# Other_funtions.net
KiCad netlist of a schematic drawn in Altium Designer
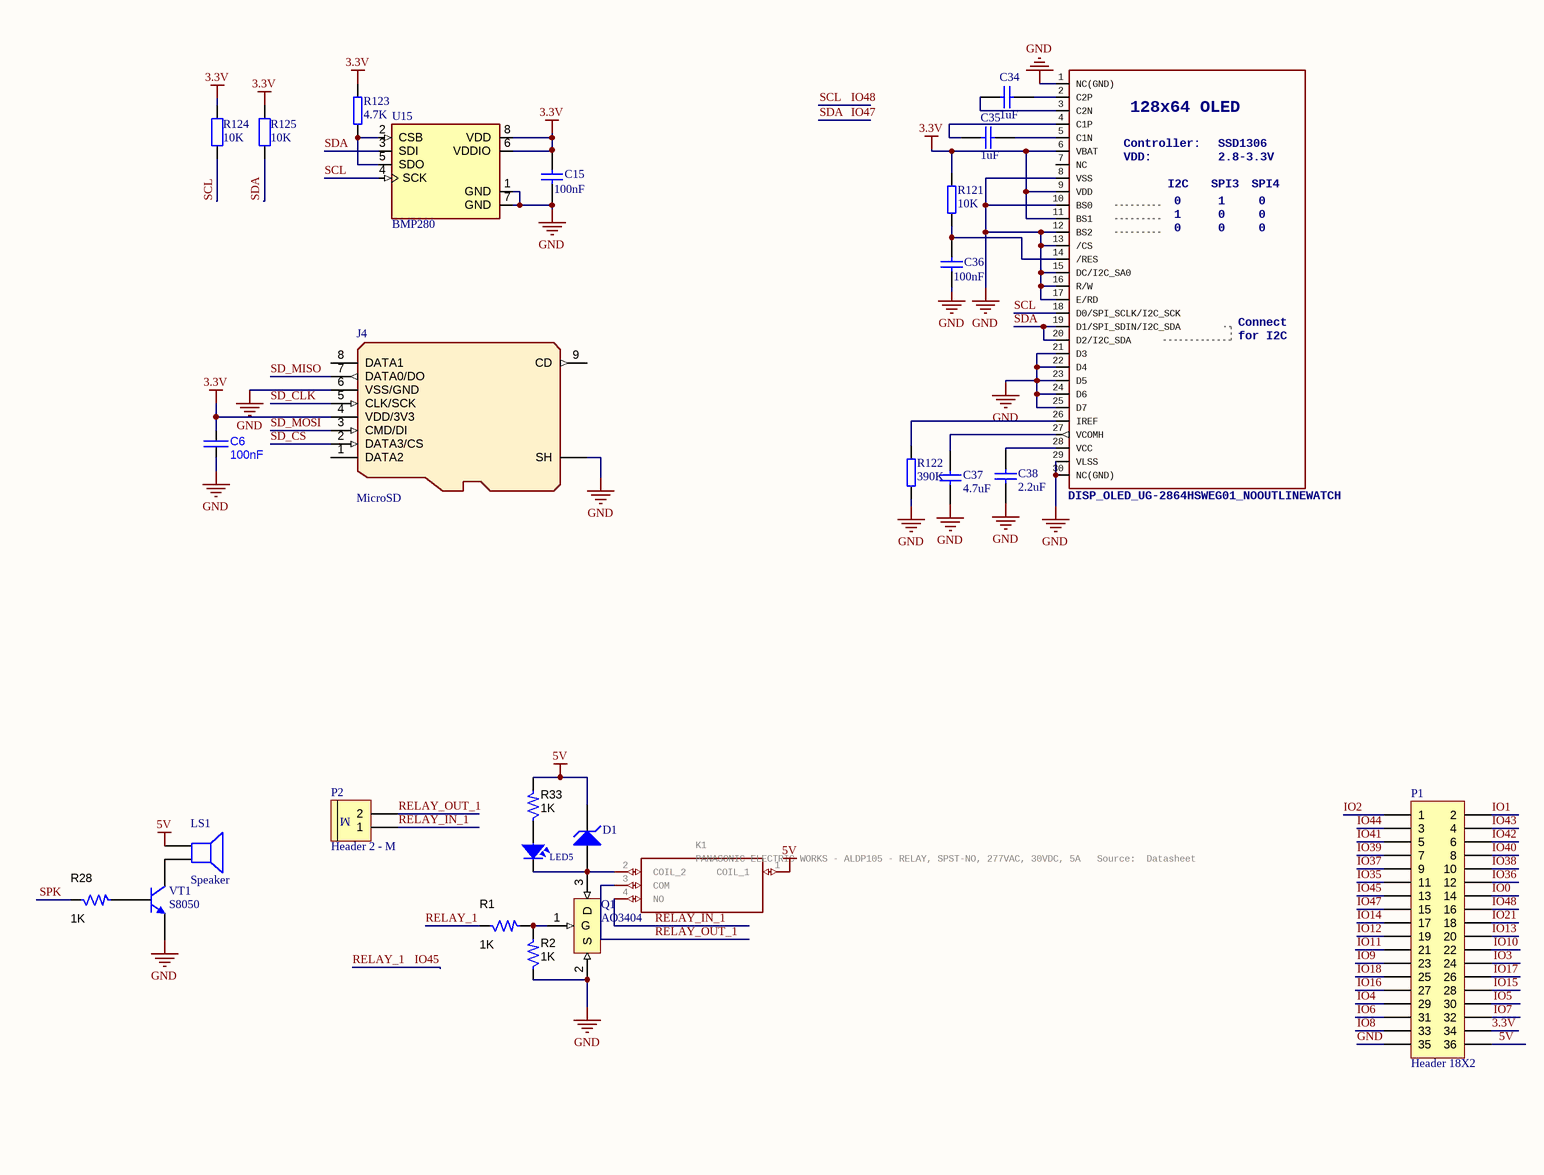
[diagram p0: Other_funtions.SchDoc, left]
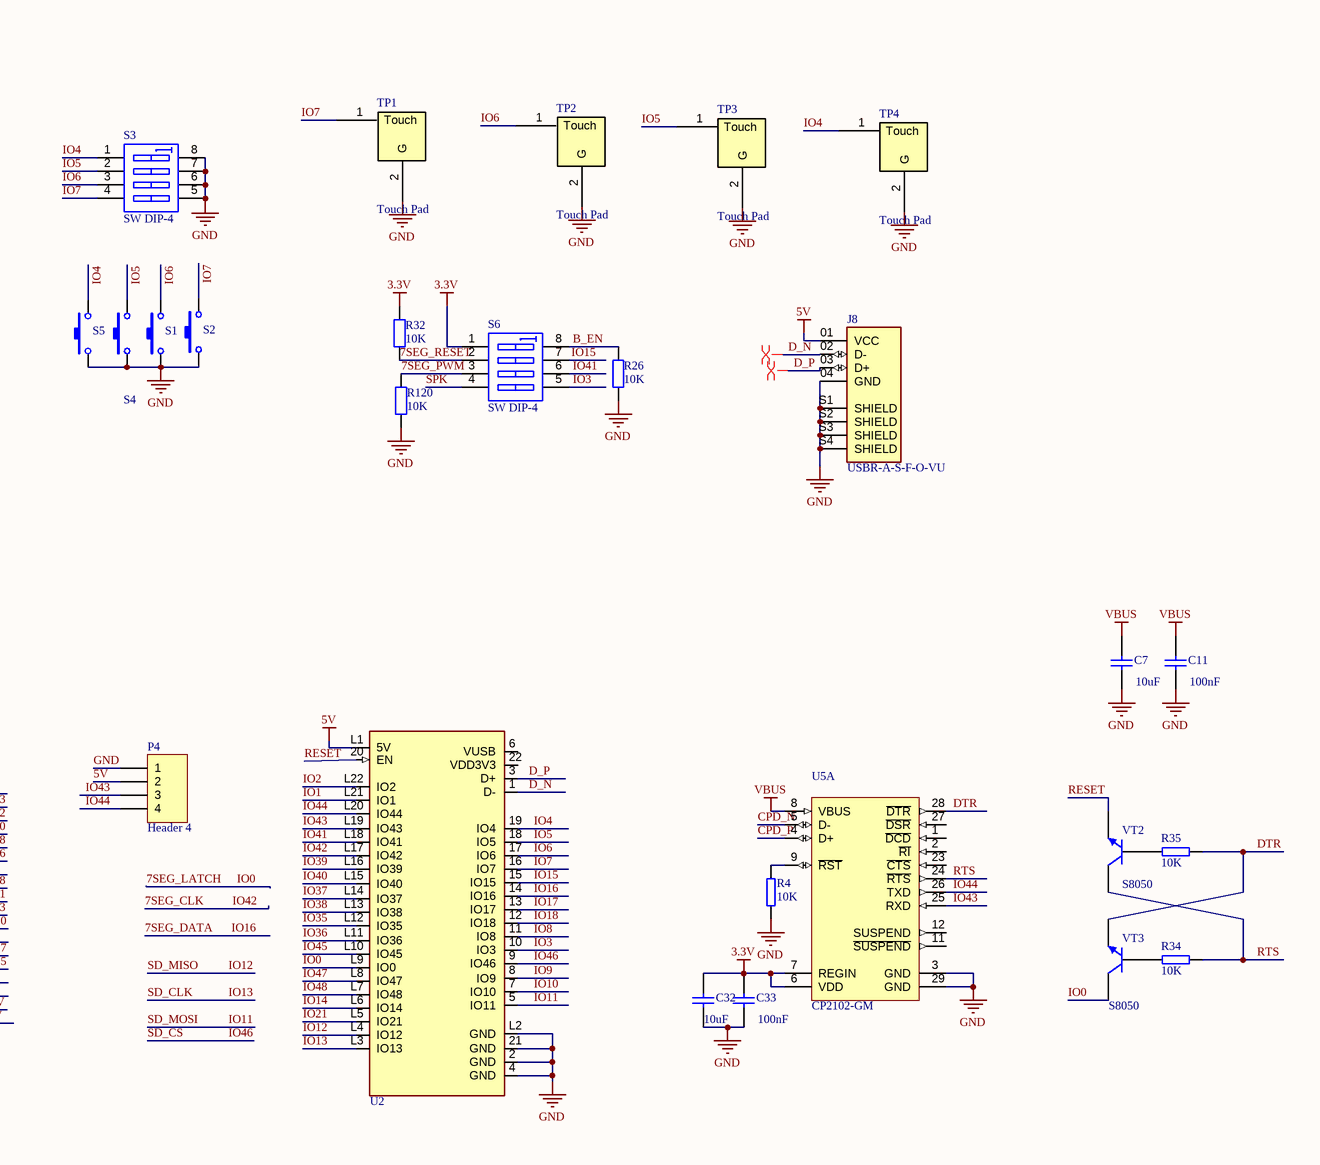
[diagram p1: Other_funtions.SchDoc, right]

(export (version "E")
  (design (tool "Eeschema 10.0.6"))
  (components
    (comp (ref "C6")
      (value "100nF")
      (footprint "CAPC2012X135N")
      (description "Capacitor SMD Cer 1.8nF 10% 50V X7R 0805")
      (fields (field (name "TOLERANCE") "±10%") (field (name "Comment") "approved sub OK"))
      (libsource (lib "WIle_dev_kit") (part "CAP C_0805"))
    )
    (comp (ref "C7")
      (value "10uF")
      (footprint "CAPC1608X90N")
      (description "CAP SM 0603 X5R 10uF 10%")
      (fields (field (name "TOLERANCE") "±10%") (field (name "Comment") "Cap Semi"))
      (libsource (lib "electronpowered") (part "CAP-SM-0603-X5R-10uF"))
    )
    (comp (ref "C11")
      (value "100nF")
      (footprint "CAPC1608X90N")
      (description "CAP SM 0603 X7R 100nF 10%")
      (fields (field (name "TOLERANCE") "±10%") (field (name "Comment") "Cap Semi"))
      (libsource (lib "electronpowered") (part "CAP-SM-0603-X7R-100nF"))
    )
    (comp (ref "C15")
      (value "100nF")
      (footprint "CAPC1608X90N")
      (description "CAP SM 0603 X7R 100nF 10%")
      (fields (field (name "TOLERANCE") "±10%") (field (name "Comment") "Cap Semi"))
      (libsource (lib "electronpowered") (part "CAP-SM-0603-X7R-100nF"))
    )
    (comp (ref "C32")
      (value "10uF")
      (footprint "CAPC1608X90N")
      (description "CAP SM 0603 X5R 10uF 10%")
      (fields (field (name "TOLERANCE") "±10%") (field (name "Comment") "Cap Semi"))
      (libsource (lib "electronpowered") (part "CAP-SM-0603-X5R-10uF"))
    )
    (comp (ref "C33")
      (value "100nF")
      (footprint "CAPC1608X90N")
      (description "CAP SM 0603 X7R 100nF 10%")
      (fields (field (name "TOLERANCE") "±10%") (field (name "Comment") "Cap Semi"))
      (libsource (lib "electronpowered") (part "CAP-SM-0603-X7R-100nF"))
    )
    (comp (ref "C34")
      (value "1uF")
      (footprint "CAPC1608X90N")
      (description "CAP SM 0603 X7R 100nF 10%")
      (fields (field (name "TOLERANCE") "±10%") (field (name "Comment") "Cap Semi"))
      (libsource (lib "electronpowered") (part "CAP-SM-0603-X7R-100nF"))
    )
    (comp (ref "C35")
      (value "1uF")
      (footprint "CAPC1608X90N")
      (description "CAP SM 0603 X7R 100nF 10%")
      (fields (field (name "TOLERANCE") "±10%") (field (name "Comment") "Cap Semi"))
      (libsource (lib "electronpowered") (part "CAP-SM-0603-X7R-100nF"))
    )
    (comp (ref "C36")
      (value "100nF")
      (footprint "CAPC1608X90N")
      (description "CAP SM 0603 X7R 100nF 10%")
      (fields (field (name "TOLERANCE") "±10%") (field (name "Comment") "Cap Semi"))
      (libsource (lib "electronpowered") (part "CAP-SM-0603-X7R-100nF"))
    )
    (comp (ref "C37")
      (value "4.7uF")
      (footprint "CAPC1608X90N")
      (description "CAP SM 0603 X7R 100nF 10%")
      (fields (field (name "TOLERANCE") "±10%") (field (name "Comment") "Cap Semi"))
      (libsource (lib "electronpowered") (part "CAP-SM-0603-X7R-100nF"))
    )
    (comp (ref "C38")
      (value "2.2uF")
      (footprint "CAPC1608X90N")
      (description "CAP SM 0603 X7R 100nF 10%")
      (fields (field (name "TOLERANCE") "±10%") (field (name "Comment") "Cap Semi"))
      (libsource (lib "electronpowered") (part "CAP-SM-0603-X7R-100nF"))
    )
    (comp (ref "D1")
      (value "Diode Zener")
      (footprint "DIODE/NOM/0.5A")
      (description "Zener Diode")
      (fields (field (name "PUBLISHER") "Altium Limited"))
      (libsource (lib "WIle_dev_kit") (part "Diode Zener"))
    )
    (comp (ref "J4")
      (value "MicroSD")
      (footprint "SDCard_Micro")
      (description "Micro SD Memory Card Connector")
      (libsource (lib "MicroSD_Connector") (part "MicroSD"))
    )
    (comp (ref "J8")
      (value "USBR-A-S-F-O-VU")
      (footprint "SAMTEC_USBR-A-S-F-O-VU")
      (description "USB-A (USB TYPE-A) USB 2.0 Receptacle Connector 4 Position Through Hole")
      (fields (field (name "MF") "Samtec"))
      (libsource (lib "USBR-A-S-F-O-VU") (part "USBR-A-S-F-O-VU"))
    )
    (comp (ref "K1")
      (value "PANASONIC ELECTRIC WORKS - ALDP105 - RELAY, SPST-NO, 277VAC, 30VDC, 5A   Source:  Datasheet")
      (footprint "ALDP")
      (fields
        (field (name "MANUFACTURER_PART_NUMBER") "ALDP105")
        (field (name "MOUSER_PART_NUMBER") "769-ALDP105")
      )
      (libsource (lib "WIle_dev_kit") (part "ALDP105"))
    )
    (comp (ref "LED5")
      (value "LED SMD")
      (footprint "SM-LED-0805-Orange")
      (libsource (lib "WIle_dev_kit") (part "LED SMD 0805"))
    )
    (comp (ref "LS1")
      (value "Speaker")
      (footprint "SPEAKER")
      (description "Loudspeaker")
      (fields (field (name "PUBLISHER") "Altium Limited"))
      (libsource (lib "My Library") (part "Speaker"))
    )
    (comp (ref "OLED1")
      (value "DISP_OLED_UG-2864HSWEG01_NOOUTLINEWATCH")
      (footprint "UG-2864HSWEG01_1.3")
      (fields
        (field (name "128X64OLED") "128x64 OLED")
        (field (name "I2C") "I2C")
        (field (name "SPI3") "SPI3")
        (field (name "0") "0")
        (field (name "0_1") "0")
        (field (name "0_2") "0")
        (field (name "0_3") "0")
        (field (name "1") "1")
        (field (name "1_1") "1")
        (field (name "CONNECT") "Connect")
        (field (name "FORI2C") "for I2C")
        (field (name "CONTROLLER") "Controller:")
        (field (name "SSD1306") "SSD1306")
        (field (name "VDD") "VDD:")
        (field (name "2.8-3.3V") "2.8-3.3V")
        (field (name "SPI4") "SPI4")
        (field (name "0_4") "0")
        (field (name "0_5") "0")
        (field (name "0_6") "0")
      )
      (libsource (lib "watch") (part "DISP_OLED_UG-2864HSWEG01_NOOUTLINEWATCH"))
    )
    (comp (ref "P1")
      (value "Header 18X2")
      (footprint "HDR2X18")
      (description "Header, 18-Pin, Dual row")
      (fields (field (name "PUBLISHER") "Altium Limited"))
      (libsource (lib "My Library") (part "Header 18X2"))
    )
    (comp (ref "P2")
      (value "Header 2 - M")
      (footprint "Medium - Header 2")
      (description "Header, 2-Pin, Medium")
      (fields (field (name "PUBLISHER") "Altium Limited"))
      (libsource (lib "My Library") (part "Header 2 - M"))
    )
    (comp (ref "P4")
      (value "Header 4")
      (footprint "HDR1X4")
      (description "Header, 4-Pin")
      (fields (field (name "PUBLISHER") "Altium Limited"))
      (libsource (lib "My Library") (part "Header 4"))
    )
    (comp (ref "Q1") (value "AO3404") (footprint "SOT23-3") (libsource (lib "WIle_dev_kit") (part "AO3404")))
    (comp (ref "R1")
      (value "1K")
      (footprint "RESC1608N_ZERO")
      (description "Resistor SMD chip 0.0 Ohm 0.1W 0603")
      (fields (field (name "TOLERANCE") "±5%"))
      (libsource (lib "WIle_dev_kit") (part "RES_0603"))
    )
    (comp (ref "R2")
      (value "1K")
      (footprint "RESC1608N_ZERO")
      (description "Resistor SMD chip 0.0 Ohm 0.1W 0603")
      (fields (field (name "TOLERANCE") "±5%"))
      (libsource (lib "WIle_dev_kit") (part "RES_0603"))
    )
    (comp (ref "R4")
      (value "10K")
      (footprint "RESC1608N_ZERO")
      (description "RES SM 0603 10K")
      (fields (field (name "Comment") "Resistor"))
      (libsource (lib "electronpowered") (part "RES-SM-0603-10K"))
    )
    (comp (ref "R26")
      (value "10K")
      (footprint "RES-0603")
      (description "Resistor")
      (fields (field (name "Comment") "Res2") (field (name "PUBLISHER") "Altium Limited"))
      (libsource (lib "Miscellaneous Devices") (part "Res2"))
    )
    (comp (ref "R28")
      (value "1K")
      (footprint "RESC1608N_ZERO")
      (description "Resistor SMD chip 0.0 Ohm 0.1W 0603")
      (fields (field (name "TOLERANCE") "±5%"))
      (libsource (lib "WIle_dev_kit") (part "RES_0603"))
    )
    (comp (ref "R32")
      (value "10K")
      (footprint "RES-0603")
      (description "Resistor")
      (fields (field (name "Comment") "Res2") (field (name "PUBLISHER") "Altium Limited"))
      (libsource (lib "Miscellaneous Devices") (part "Res2"))
    )
    (comp (ref "R33")
      (value "1K")
      (footprint "RESC1608N_ZERO")
      (description "Resistor SMD chip 0.0 Ohm 0.1W 0603")
      (fields (field (name "TOLERANCE") "±5%"))
      (libsource (lib "WIle_dev_kit") (part "RES_0603"))
    )
    (comp (ref "R34")
      (value "10K")
      (footprint "RESC1608N_ZERO")
      (description "RES SM 0603 10K")
      (fields (field (name "Comment") "Resistor"))
      (libsource (lib "electronpowered") (part "RES-SM-0603-10K"))
    )
    (comp (ref "R35")
      (value "10K")
      (footprint "RESC1608N_ZERO")
      (description "RES SM 0603 10K")
      (fields (field (name "Comment") "Resistor"))
      (libsource (lib "electronpowered") (part "RES-SM-0603-10K"))
    )
    (comp (ref "R120")
      (value "10K")
      (footprint "RES-0603")
      (description "Resistor")
      (fields (field (name "Comment") "Res2") (field (name "PUBLISHER") "Altium Limited"))
      (libsource (lib "Miscellaneous Devices") (part "Res2"))
    )
    (comp (ref "R121")
      (value "10K")
      (footprint "RESC1608N_ZERO")
      (description "RES SM 0603 10K")
      (fields (field (name "Comment") "Resistor"))
      (libsource (lib "electronpowered") (part "RES-SM-0603-10K"))
    )
    (comp (ref "R122")
      (value "390K")
      (footprint "RESC1608N_ZERO")
      (description "RES SM 0603 10K")
      (fields (field (name "Comment") "Resistor"))
      (libsource (lib "electronpowered") (part "RES-SM-0603-10K"))
    )
    (comp (ref "R123")
      (value "4.7K")
      (footprint "RESC1608N_ZERO")
      (description "RES SM 0603 10K")
      (fields (field (name "Comment") "Resistor"))
      (libsource (lib "electronpowered") (part "RES-SM-0603-10K"))
    )
    (comp (ref "R124")
      (value "10K")
      (footprint "RES-0603")
      (description "Resistor")
      (fields (field (name "Comment") "Res2") (field (name "PUBLISHER") "Altium Limited"))
      (libsource (lib "Miscellaneous Devices") (part "Res2"))
    )
    (comp (ref "R125")
      (value "10K")
      (footprint "RES-0603")
      (description "Resistor")
      (fields (field (name "Comment") "Res2") (field (name "PUBLISHER") "Altium Limited"))
      (libsource (lib "Miscellaneous Devices") (part "Res2"))
    )
    (comp (ref "S1")
      (value "SW-SMD")
      (footprint "SW-SMD")
      (description "Switch")
      (fields (field (name "PUBLISHER") "Altium Limited"))
      (libsource (lib "My Library") (part "SW-SMD"))
    )
    (comp (ref "S2")
      (value "SW-SMD")
      (footprint "SW-SMD")
      (description "Switch")
      (fields (field (name "PUBLISHER") "Altium Limited"))
      (libsource (lib "My Library") (part "SW-SMD"))
    )
    (comp (ref "S3")
      (value "SW DIP-4")
      (footprint "DIPSWITCH4")
      (description "DIP Switch, 4 Position, SPST")
      (fields (field (name "PUBLISHER") "Altium Limited"))
      (libsource (lib "My Library") (part "SW DIP-4"))
    )
    (comp (ref "S4")
      (value "SW-SMD")
      (footprint "SW-SMD")
      (description "Switch")
      (fields (field (name "PUBLISHER") "Altium Limited"))
      (libsource (lib "My Library") (part "SW-SMD"))
    )
    (comp (ref "S5")
      (value "SW-SMD")
      (footprint "SW-SMD")
      (description "Switch")
      (fields (field (name "PUBLISHER") "Altium Limited"))
      (libsource (lib "My Library") (part "SW-SMD"))
    )
    (comp (ref "S6")
      (value "SW DIP-4")
      (footprint "DIPSWITCH4")
      (description "DIP Switch, 4 Position, SPST")
      (fields (field (name "PUBLISHER") "Altium Limited"))
      (libsource (lib "My Library") (part "SW DIP-4"))
    )
    (comp (ref "TP1")
      (value "Touch Pad")
      (footprint "Touch Pad")
      (libsource (lib "WIle_dev_kit") (part "Touch Pad"))
    )
    (comp (ref "TP2")
      (value "Touch Pad")
      (footprint "Touch Pad")
      (libsource (lib "WIle_dev_kit") (part "Touch Pad"))
    )
    (comp (ref "TP3")
      (value "Touch Pad")
      (footprint "Touch Pad")
      (libsource (lib "WIle_dev_kit") (part "Touch Pad"))
    )
    (comp (ref "TP4")
      (value "Touch Pad")
      (footprint "Touch Pad")
      (libsource (lib "WIle_dev_kit") (part "Touch Pad"))
    )
    (comp (ref "U2")
      (value "ESP32S3_CONTROLLER")
      (footprint "ESP32S3_controller")
      (libsource (lib "WIle_dev_kit") (part "ESP32S3_CONTROLLER"))
    )
    (comp (ref "U5")
      (value "CP2102-GM")
      (footprint "CP2102")
      (description "Single-Chip USB to UART Bridge, 1024 Bytes EEPROM, -40 to 85 degC, 28-pin QFN, Tube")
      (fields (field (name "MANUFACTURER") "Silicon Labs"))
      (libsource (lib "Silicon Labs Interface") (part "CP2102-GM"))
    )
    (comp (ref "U15")
      (value "BMP280")
      (footprint "XDCR_BMP280")
      (description "BMP280 Absolute Barometric Pressure Sensor for Battery Powered Devices 2 x 2.5mm")
      (libsource (lib "BMP280") (part "BMP280"))
    )
    (comp (ref "VT1")
      (value "S8050")
      (footprint "SMT_TRIODE_NPN")
      (description "Surface mount NPN transistor, package SOT-23")
      (libsource (lib "WIle_dev_kit") (part "SMT_TRIODE_NPN"))
    )
    (comp (ref "VT2")
      (value "S8050")
      (footprint "SMT_TRIODE_NPN")
      (description "Surface mount NPN transistor, package SOT-23")
      (libsource (lib "NODEMCU_DEVKIT_V1.0") (part "SMT_TRIODE_NPN"))
    )
    (comp (ref "VT3")
      (value "S8050")
      (footprint "SMT_TRIODE_NPN")
      (description "Surface mount NPN transistor, package SOT-23")
      (libsource (lib "NODEMCU_DEVKIT_V1.0") (part "SMT_TRIODE_NPN"))
    )
  )
  (nets
    (net (code "1") (name "/7SEG_CLK") (class "Default")
      (node (ref "P1") (pin "6") (pinfunction "6_6") (pintype "passive"))
      (node (ref "U2") (pin "L17") (pinfunction "IO42_L17") (pintype "bidirectional"))
    )
    (net (code "2") (name "/7SEG_DATA") (class "Default")
      (node (ref "P1") (pin "27") (pinfunction "27_27") (pintype "passive"))
      (node (ref "U2") (pin "14") (pinfunction "IO16_14") (pintype "bidirectional"))
    )
    (net (code "3") (name "/7SEG_LATCH") (class "Default")
      (node (ref "P1") (pin "14") (pinfunction "14_14") (pintype "passive"))
      (node (ref "U2") (pin "L9") (pinfunction "IO0_L9") (pintype "bidirectional"))
      (node (ref "VT3") (pin "3") (pinfunction "C_3") (pintype "passive"))
    )
    (net (code "4") (name "/7SEG_PWM") (class "Default")
      (node (ref "R120") (pin "1") (pinfunction "1_1") (pintype "passive"))
      (node (ref "S6") (pin "3") (pinfunction "A3_3") (pintype "passive"))
    )
    (net (code "5") (name "/7SEG_RESET") (class "Default")
      (node (ref "R32") (pin "2") (pinfunction "2_2") (pintype "passive"))
      (node (ref "S6") (pin "2") (pinfunction "A2_2") (pintype "passive"))
    )
    (net (code "6") (name "/B_EN") (class "Default")
      (node (ref "R26") (pin "1") (pinfunction "1_1") (pintype "passive"))
      (node (ref "S6") (pin "8") (pinfunction "B1_8") (pintype "passive"))
    )
    (net (code "7") (name "/CPD_N") (class "Default")
      (node (ref "U5") (pin "5") (pinfunction "D-_5") (pintype "bidirectional"))
    )
    (net (code "8") (name "/CPD_P") (class "Default")
      (node (ref "U5") (pin "4") (pinfunction "D+_4") (pintype "bidirectional"))
    )
    (net (code "9") (name "/DTR") (class "Default")
      (node (ref "R35") (pin "2") (pinfunction "2_2") (pintype "passive"))
      (node (ref "U5") (pin "28") (pinfunction "~{DTR}_28") (pintype "output"))
      (node (ref "VT3") (pin "2") (pinfunction "E_2") (pintype "passive"))
    )
    (net (code "10") (name "/D_N") (class "Default")
      (node (ref "J8") (pin "02") (pinfunction "D-_02") (pintype "bidirectional"))
      (node (ref "U2") (pin "1") (pinfunction "D-_1") (pintype "bidirectional"))
    )
    (net (code "11") (name "/D_P") (class "Default")
      (node (ref "J8") (pin "03") (pinfunction "D+_03") (pintype "bidirectional"))
      (node (ref "U2") (pin "3") (pinfunction "D+_3") (pintype "bidirectional"))
    )
    (net (code "12") (name "/IO1") (class "Default")
      (node (ref "P1") (pin "2") (pinfunction "2_2") (pintype "passive"))
      (node (ref "U2") (pin "L21") (pinfunction "IO1_L21") (pintype "bidirectional"))
    )
    (net (code "13") (name "/IO2") (class "Default")
      (node (ref "P1") (pin "1") (pinfunction "1_1") (pintype "passive"))
      (node (ref "U2") (pin "L22") (pinfunction "IO2_L22") (pintype "bidirectional"))
    )
    (net (code "14") (name "/IO3") (class "Default")
      (node (ref "P1") (pin "24") (pinfunction "24_24") (pintype "passive"))
      (node (ref "S6") (pin "5") (pinfunction "B4_5") (pintype "passive"))
      (node (ref "U2") (pin "10") (pinfunction "IO3_10") (pintype "bidirectional"))
    )
    (net (code "15") (name "/IO4") (class "Default")
      (node (ref "P1") (pin "29") (pinfunction "29_29") (pintype "passive"))
      (node (ref "S3") (pin "1") (pinfunction "A1_1") (pintype "passive"))
      (node (ref "S5") (pin "2") (pinfunction "2_2") (pintype "passive"))
      (node (ref "TP4") (pin "1") (pinfunction "Touch_1") (pintype "passive"))
      (node (ref "U2") (pin "19") (pinfunction "IO4_19") (pintype "bidirectional"))
    )
    (net (code "16") (name "/IO5") (class "Default")
      (node (ref "P1") (pin "30") (pinfunction "30_30") (pintype "passive"))
      (node (ref "S3") (pin "2") (pinfunction "A2_2") (pintype "passive"))
      (node (ref "S4") (pin "2") (pinfunction "2_2") (pintype "passive"))
      (node (ref "TP3") (pin "1") (pinfunction "Touch_1") (pintype "passive"))
      (node (ref "U2") (pin "18") (pinfunction "IO5_18") (pintype "bidirectional"))
    )
    (net (code "17") (name "/IO6") (class "Default")
      (node (ref "P1") (pin "31") (pinfunction "31_31") (pintype "passive"))
      (node (ref "S1") (pin "2") (pinfunction "2_2") (pintype "passive"))
      (node (ref "S3") (pin "3") (pinfunction "A3_3") (pintype "passive"))
      (node (ref "TP2") (pin "1") (pinfunction "Touch_1") (pintype "passive"))
      (node (ref "U2") (pin "17") (pinfunction "IO6_17") (pintype "bidirectional"))
    )
    (net (code "18") (name "/IO7") (class "Default")
      (node (ref "P1") (pin "32") (pinfunction "32_32") (pintype "passive"))
      (node (ref "S2") (pin "2") (pinfunction "2_2") (pintype "passive"))
      (node (ref "S3") (pin "4") (pinfunction "A4_4") (pintype "passive"))
      (node (ref "TP1") (pin "1") (pinfunction "Touch_1") (pintype "passive"))
      (node (ref "U2") (pin "16") (pinfunction "IO7_16") (pintype "bidirectional"))
    )
    (net (code "19") (name "/IO8") (class "Default")
      (node (ref "P1") (pin "33") (pinfunction "33_33") (pintype "passive"))
      (node (ref "U2") (pin "11") (pinfunction "IO8_11") (pintype "bidirectional"))
    )
    (net (code "20") (name "/IO9") (class "Default")
      (node (ref "P1") (pin "23") (pinfunction "23_23") (pintype "passive"))
      (node (ref "U2") (pin "8") (pinfunction "IO9_8") (pintype "bidirectional"))
    )
    (net (code "21") (name "/IO10") (class "Default")
      (node (ref "P1") (pin "22") (pinfunction "22_22") (pintype "passive"))
      (node (ref "U2") (pin "7") (pinfunction "IO10_7") (pintype "bidirectional"))
    )
    (net (code "22") (name "/IO11") (class "Default")
      (node (ref "J4") (pin "3") (pinfunction "CMD/DI_3") (pintype "input"))
      (node (ref "P1") (pin "21") (pinfunction "21_21") (pintype "passive"))
      (node (ref "U2") (pin "5") (pinfunction "IO11_5") (pintype "bidirectional"))
    )
    (net (code "23") (name "/IO12") (class "Default")
      (node (ref "J4") (pin "7") (pinfunction "DATA0/DO_7") (pintype "output"))
      (node (ref "P1") (pin "19") (pinfunction "19_19") (pintype "passive"))
      (node (ref "U2") (pin "L4") (pinfunction "IO12_L4") (pintype "bidirectional"))
    )
    (net (code "24") (name "/IO13") (class "Default")
      (node (ref "J4") (pin "5") (pinfunction "CLK/SCK_5") (pintype "input"))
      (node (ref "P1") (pin "20") (pinfunction "20_20") (pintype "passive"))
      (node (ref "U2") (pin "L3") (pinfunction "IO13_L3") (pintype "bidirectional"))
    )
    (net (code "25") (name "/IO14") (class "Default")
      (node (ref "P1") (pin "17") (pinfunction "17_17") (pintype "passive"))
      (node (ref "U2") (pin "L6") (pinfunction "IO14_L6") (pintype "bidirectional"))
    )
    (net (code "26") (name "/IO15") (class "Default")
      (node (ref "P1") (pin "28") (pinfunction "28_28") (pintype "passive"))
      (node (ref "S6") (pin "7") (pinfunction "B2_7") (pintype "passive"))
      (node (ref "U2") (pin "15") (pinfunction "IO15_15") (pintype "bidirectional"))
    )
    (net (code "27") (name "/IO17") (class "Default")
      (node (ref "P1") (pin "26") (pinfunction "26_26") (pintype "passive"))
      (node (ref "U2") (pin "13") (pinfunction "IO17_13") (pintype "bidirectional"))
    )
    (net (code "28") (name "/IO18") (class "Default")
      (node (ref "P1") (pin "25") (pinfunction "25_25") (pintype "passive"))
      (node (ref "U2") (pin "12") (pinfunction "IO18_12") (pintype "bidirectional"))
    )
    (net (code "29") (name "/IO21") (class "Default")
      (node (ref "P1") (pin "18") (pinfunction "18_18") (pintype "passive"))
      (node (ref "U2") (pin "L5") (pinfunction "IO21_L5") (pintype "bidirectional"))
    )
    (net (code "30") (name "/IO35") (class "Default")
      (node (ref "P1") (pin "11") (pinfunction "11_11") (pintype "passive"))
      (node (ref "U2") (pin "L12") (pinfunction "IO35_L12") (pintype "bidirectional"))
    )
    (net (code "31") (name "/IO36") (class "Default")
      (node (ref "P1") (pin "12") (pinfunction "12_12") (pintype "passive"))
      (node (ref "U2") (pin "L11") (pinfunction "IO36_L11") (pintype "bidirectional"))
    )
    (net (code "32") (name "/IO37") (class "Default")
      (node (ref "P1") (pin "9") (pinfunction "9_9") (pintype "passive"))
      (node (ref "U2") (pin "L14") (pinfunction "IO37_L14") (pintype "bidirectional"))
    )
    (net (code "33") (name "/IO38") (class "Default")
      (node (ref "P1") (pin "10") (pinfunction "10_10") (pintype "passive"))
      (node (ref "U2") (pin "L13") (pinfunction "IO38_L13") (pintype "bidirectional"))
    )
    (net (code "34") (name "/IO39") (class "Default")
      (node (ref "P1") (pin "7") (pinfunction "7_7") (pintype "passive"))
      (node (ref "U2") (pin "L16") (pinfunction "IO39_L16") (pintype "bidirectional"))
    )
    (net (code "35") (name "/IO40") (class "Default")
      (node (ref "P1") (pin "8") (pinfunction "8_8") (pintype "passive"))
      (node (ref "U2") (pin "L15") (pinfunction "IO40_L15") (pintype "bidirectional"))
    )
    (net (code "36") (name "/IO41") (class "Default")
      (node (ref "P1") (pin "5") (pinfunction "5_5") (pintype "passive"))
      (node (ref "S6") (pin "6") (pinfunction "B3_6") (pintype "passive"))
      (node (ref "U2") (pin "L18") (pinfunction "IO41_L18") (pintype "bidirectional"))
    )
    (net (code "37") (name "/IO43") (class "Default")
      (node (ref "P1") (pin "4") (pinfunction "4_4") (pintype "passive"))
      (node (ref "P4") (pin "3") (pinfunction "3_3") (pintype "passive"))
      (node (ref "U2") (pin "L19") (pinfunction "IO43_L19") (pintype "bidirectional"))
      (node (ref "U5") (pin "25") (pinfunction "RXD_25") (pintype "input"))
    )
    (net (code "38") (name "/IO44") (class "Default")
      (node (ref "P1") (pin "3") (pinfunction "3_3") (pintype "passive"))
      (node (ref "P4") (pin "4") (pinfunction "4_4") (pintype "passive"))
      (node (ref "U2") (pin "L20") (pinfunction "IO44_L20") (pintype "bidirectional"))
      (node (ref "U5") (pin "26") (pinfunction "TXD_26") (pintype "output"))
    )
    (net (code "39") (name "/IO45") (class "Default")
      (node (ref "P1") (pin "13") (pinfunction "13_13") (pintype "passive"))
      (node (ref "R1") (pin "1") (pinfunction "1_1") (pintype "passive"))
      (node (ref "U2") (pin "L10") (pinfunction "IO45_L10") (pintype "bidirectional"))
    )
    (net (code "40") (name "/IO46") (class "Default")
      (node (ref "J4") (pin "2") (pinfunction "DATA3/CS_2") (pintype "input"))
      (node (ref "U2") (pin "9") (pinfunction "IO46_9") (pintype "bidirectional"))
    )
    (net (code "41") (name "/IO47") (class "Default")
      (node (ref "OLED1") (pin "19") (pinfunction "D1/SPI_SDIN/I2C_SDA_19") (pintype "passive"))
      (node (ref "OLED1") (pin "20") (pinfunction "D2/I2C_SDA_20") (pintype "passive"))
      (node (ref "P1") (pin "15") (pinfunction "15_15") (pintype "passive"))
      (node (ref "R125") (pin "2") (pinfunction "2_2") (pintype "passive"))
      (node (ref "U15") (pin "3") (pinfunction "SDI_3") (pintype "bidirectional"))
      (node (ref "U2") (pin "L8") (pinfunction "IO47_L8") (pintype "bidirectional"))
    )
    (net (code "42") (name "/IO48") (class "Default")
      (node (ref "OLED1") (pin "18") (pinfunction "D0/SPI_SCLK/I2C_SCK_18") (pintype "passive"))
      (node (ref "P1") (pin "16") (pinfunction "16_16") (pintype "passive"))
      (node (ref "R124") (pin "2") (pinfunction "2_2") (pintype "passive"))
      (node (ref "U15") (pin "4") (pinfunction "SCK_4") (pintype "input"))
      (node (ref "U2") (pin "L7") (pinfunction "IO48_L7") (pintype "bidirectional"))
    )
    (net (code "43") (name "/RELAY_IN_1") (class "Default")
      (node (ref "K1") (pin "4") (pinfunction "NO_4") (pintype "bidirectional"))
      (node (ref "P2") (pin "1") (pinfunction "1_1") (pintype "passive"))
    )
    (net (code "44") (name "/RELAY_OUT_1") (class "Default")
      (node (ref "K1") (pin "3") (pinfunction "COM_3") (pintype "bidirectional"))
      (node (ref "P2") (pin "2") (pinfunction "2_2") (pintype "passive"))
    )
    (net (code "45") (name "/RESET") (class "Default")
      (node (ref "U2") (pin "20") (pinfunction "EN_20") (pintype "input"))
      (node (ref "VT2") (pin "2") (pinfunction "E_2") (pintype "passive"))
    )
    (net (code "46") (name "/RTS") (class "Default")
      (node (ref "R34") (pin "1") (pinfunction "1_1") (pintype "passive"))
      (node (ref "U5") (pin "24") (pinfunction "~{RTS}_24") (pintype "output"))
      (node (ref "VT2") (pin "3") (pinfunction "C_3") (pintype "passive"))
    )
    (net (code "47") (name "/SPK") (class "Default")
      (node (ref "R28") (pin "1") (pinfunction "1_1") (pintype "passive"))
      (node (ref "S6") (pin "4") (pinfunction "A4_4") (pintype "passive"))
    )
    (net (code "48") (name "3.3V") (class "Default")
      (node (ref "C15") (pin "2") (pinfunction "2_2") (pintype "passive"))
      (node (ref "C32") (pin "2") (pinfunction "2_2") (pintype "passive"))
      (node (ref "C33") (pin "2") (pinfunction "2_2") (pintype "passive"))
      (node (ref "C6") (pin "2") (pintype "passive"))
      (node (ref "J4") (pin "4") (pinfunction "VDD/3V3_4") (pintype "power_in"))
      (node (ref "OLED1") (pin "11") (pinfunction "BS1_11") (pintype "passive"))
      (node (ref "OLED1") (pin "6") (pinfunction "VBAT_6") (pintype "passive"))
      (node (ref "OLED1") (pin "9") (pinfunction "VDD_9") (pintype "power_in"))
      (node (ref "P1") (pin "34") (pinfunction "34_34") (pintype "passive"))
      (node (ref "R121") (pin "1") (pinfunction "1_1") (pintype "passive"))
      (node (ref "R123") (pin "2") (pinfunction "2_2") (pintype "passive"))
      (node (ref "R124") (pin "1") (pinfunction "1_1") (pintype "passive"))
      (node (ref "R125") (pin "1") (pinfunction "1_1") (pintype "passive"))
      (node (ref "R32") (pin "1") (pinfunction "1_1") (pintype "passive"))
      (node (ref "S6") (pin "1") (pinfunction "A1_1") (pintype "passive"))
      (node (ref "U15") (pin "6") (pinfunction "VDDIO_6") (pintype "power_in"))
      (node (ref "U15") (pin "8") (pinfunction "VDD_8") (pintype "power_in"))
      (node (ref "U5") (pin "6") (pinfunction "VDD_6") (pintype "power_in"))
      (node (ref "U5") (pin "7") (pinfunction "REGIN_7") (pintype "power_in"))
    )
    (net (code "49") (name "5V") (class "Default")
      (node (ref "D1") (pin "2") (pinfunction "K_2") (pintype "passive"))
      (node (ref "J8") (pin "01") (pinfunction "VCC_01") (pintype "power_in"))
      (node (ref "K1") (pin "1") (pinfunction "COIL_1_1") (pintype "bidirectional"))
      (node (ref "LS1") (pin "1") (pinfunction "1_1") (pintype "passive"))
      (node (ref "P1") (pin "36") (pinfunction "36_36") (pintype "passive"))
      (node (ref "P4") (pin "2") (pinfunction "2_2") (pintype "passive"))
      (node (ref "R33") (pin "2") (pinfunction "2_2") (pintype "passive"))
      (node (ref "U2") (pin "L1") (pinfunction "5V_L1") (pintype "power_in"))
    )
    (net (code "50") (name "GND") (class "Default")
      (node (ref "C11") (pin "1") (pinfunction "1_1") (pintype "passive"))
      (node (ref "C15") (pin "1") (pinfunction "1_1") (pintype "passive"))
      (node (ref "C32") (pin "1") (pinfunction "1_1") (pintype "passive"))
      (node (ref "C33") (pin "1") (pinfunction "1_1") (pintype "passive"))
      (node (ref "C36") (pin "1") (pinfunction "1_1") (pintype "passive"))
      (node (ref "C37") (pin "2") (pinfunction "2_2") (pintype "passive"))
      (node (ref "C38") (pin "2") (pinfunction "2_2") (pintype "passive"))
      (node (ref "C6") (pin "1") (pintype "passive"))
      (node (ref "C7") (pin "1") (pinfunction "1_1") (pintype "passive"))
      (node (ref "J4") (pin "6") (pinfunction "VSS/GND_6") (pintype "power_in"))
      (node (ref "J4") (pin "SH") (pinfunction "SH_SH") (pintype "passive"))
      (node (ref "J8") (pin "04") (pinfunction "GND_04") (pintype "power_in"))
      (node (ref "J8") (pin "S1") (pinfunction "SHIELD_S1") (pintype "passive"))
      (node (ref "J8") (pin "S2") (pinfunction "SHIELD_S2") (pintype "passive"))
      (node (ref "J8") (pin "S3") (pinfunction "SHIELD_S3") (pintype "passive"))
      (node (ref "J8") (pin "S4") (pinfunction "SHIELD_S4") (pintype "passive"))
      (node (ref "OLED1") (pin "1") (pinfunction "NC(GND)_1") (pintype "passive"))
      (node (ref "OLED1") (pin "10") (pinfunction "BS0_10") (pintype "passive"))
      (node (ref "OLED1") (pin "12") (pinfunction "BS2_12") (pintype "passive"))
      (node (ref "OLED1") (pin "13") (pinfunction "/CS_13") (pintype "passive"))
      (node (ref "OLED1") (pin "15") (pinfunction "DC/I2C_SA0_15") (pintype "passive"))
      (node (ref "OLED1") (pin "16") (pinfunction "R/W_16") (pintype "passive"))
      (node (ref "OLED1") (pin "17") (pinfunction "E/RD_17") (pintype "passive"))
      (node (ref "OLED1") (pin "21") (pinfunction "D3_21") (pintype "passive"))
      (node (ref "OLED1") (pin "22") (pinfunction "D4_22") (pintype "passive"))
      (node (ref "OLED1") (pin "23") (pinfunction "D5_23") (pintype "passive"))
      (node (ref "OLED1") (pin "24") (pinfunction "D6_24") (pintype "passive"))
      (node (ref "OLED1") (pin "25") (pinfunction "D7_25") (pintype "passive"))
      (node (ref "OLED1") (pin "29") (pinfunction "VLSS_29") (pintype "power_in"))
      (node (ref "OLED1") (pin "30") (pinfunction "NC(GND)_30") (pintype "passive"))
      (node (ref "OLED1") (pin "8") (pinfunction "VSS_8") (pintype "power_in"))
      (node (ref "P1") (pin "35") (pinfunction "35_35") (pintype "passive"))
      (node (ref "P4") (pin "1") (pinfunction "1_1") (pintype "passive"))
      (node (ref "Q1") (pin "2") (pinfunction "S_2") (pintype "input"))
      (node (ref "R120") (pin "2") (pinfunction "2_2") (pintype "passive"))
      (node (ref "R122") (pin "2") (pinfunction "2_2") (pintype "passive"))
      (node (ref "R2") (pin "1") (pinfunction "1_1") (pintype "passive"))
      (node (ref "R26") (pin "2") (pinfunction "2_2") (pintype "passive"))
      (node (ref "R4") (pin "2") (pinfunction "2_2") (pintype "passive"))
      (node (ref "S1") (pin "1") (pinfunction "1_1") (pintype "passive"))
      (node (ref "S2") (pin "1") (pinfunction "1_1") (pintype "passive"))
      (node (ref "S3") (pin "5") (pinfunction "B4_5") (pintype "passive"))
      (node (ref "S3") (pin "6") (pinfunction "B3_6") (pintype "passive"))
      (node (ref "S3") (pin "7") (pinfunction "B2_7") (pintype "passive"))
      (node (ref "S3") (pin "8") (pinfunction "B1_8") (pintype "passive"))
      (node (ref "S4") (pin "1") (pinfunction "1_1") (pintype "passive"))
      (node (ref "S5") (pin "1") (pinfunction "1_1") (pintype "passive"))
      (node (ref "TP1") (pin "2") (pinfunction "G_2") (pintype "passive"))
      (node (ref "TP2") (pin "2") (pinfunction "G_2") (pintype "passive"))
      (node (ref "TP3") (pin "2") (pinfunction "G_2") (pintype "passive"))
      (node (ref "TP4") (pin "2") (pinfunction "G_2") (pintype "passive"))
      (node (ref "U15") (pin "1") (pinfunction "GND_1") (pintype "power_in"))
      (node (ref "U15") (pin "7") (pinfunction "GND_7") (pintype "power_in"))
      (node (ref "U2") (pin "2") (pinfunction "GND_2") (pintype "power_in"))
      (node (ref "U2") (pin "21") (pinfunction "GND_21") (pintype "power_in"))
      (node (ref "U2") (pin "4") (pinfunction "GND_4") (pintype "power_in"))
      (node (ref "U2") (pin "L2") (pinfunction "GND_L2") (pintype "power_in"))
      (node (ref "U5") (pin "29") (pinfunction "GND_29") (pintype "power_in"))
      (node (ref "U5") (pin "3") (pinfunction "GND_3") (pintype "power_in"))
      (node (ref "VT1") (pin "2") (pinfunction "E_2") (pintype "passive"))
    )
    (net (code "51") (name "Net-(D1-A)") (class "Default")
      (node (ref "D1") (pin "1") (pinfunction "A_1") (pintype "passive"))
      (node (ref "K1") (pin "2") (pinfunction "COIL_2_2") (pintype "bidirectional"))
      (node (ref "LED5") (pin "2") (pinfunction "2_2") (pintype "passive"))
      (node (ref "Q1") (pin "3") (pinfunction "D_3") (pintype "input"))
    )
    (net (code "52") (name "Net-(LED5-Pad1)") (class "Default")
      (node (ref "LED5") (pin "1") (pinfunction "1_1") (pintype "passive"))
      (node (ref "R33") (pin "1") (pinfunction "1_1") (pintype "passive"))
    )
    (net (code "53") (name "Net-(OLED1-C1N)") (class "Default")
      (node (ref "C35") (pin "1") (pinfunction "1_1") (pintype "passive"))
      (node (ref "OLED1") (pin "5") (pinfunction "C1N_5") (pintype "passive"))
    )
    (net (code "54") (name "Net-(OLED1-C1P)") (class "Default")
      (node (ref "C35") (pin "2") (pinfunction "2_2") (pintype "passive"))
      (node (ref "OLED1") (pin "4") (pinfunction "C1P_4") (pintype "passive"))
    )
    (net (code "55") (name "Net-(OLED1-C2N)") (class "Default")
      (node (ref "C34") (pin "2") (pinfunction "2_2") (pintype "passive"))
      (node (ref "OLED1") (pin "3") (pinfunction "C2N_3") (pintype "passive"))
    )
    (net (code "56") (name "Net-(OLED1-C2P)") (class "Default")
      (node (ref "C34") (pin "1") (pinfunction "1_1") (pintype "passive"))
      (node (ref "OLED1") (pin "2") (pinfunction "C2P_2") (pintype "passive"))
    )
    (net (code "57") (name "Net-(OLED1-IREF)") (class "Default")
      (node (ref "OLED1") (pin "26") (pinfunction "IREF_26") (pintype "passive"))
      (node (ref "R122") (pin "1") (pinfunction "1_1") (pintype "passive"))
    )
    (net (code "58") (name "Net-(OLED1-VCC)") (class "Default")
      (node (ref "C38") (pin "1") (pinfunction "1_1") (pintype "passive"))
      (node (ref "OLED1") (pin "28") (pinfunction "VCC_28") (pintype "power_in"))
    )
    (net (code "59") (name "Net-(OLED1-VCOMH)") (class "Default")
      (node (ref "C37") (pin "1") (pinfunction "1_1") (pintype "passive"))
      (node (ref "OLED1") (pin "27") (pinfunction "VCOMH_27") (pintype "output"))
    )
    (net (code "60") (name "Net-(OLED1-{slash}RES)") (class "Default")
      (node (ref "C36") (pin "2") (pinfunction "2_2") (pintype "passive"))
      (node (ref "OLED1") (pin "14") (pinfunction "/RES_14") (pintype "passive"))
      (node (ref "R121") (pin "2") (pinfunction "2_2") (pintype "passive"))
    )
    (net (code "61") (name "Net-(Q1-G)") (class "Default")
      (node (ref "Q1") (pin "1") (pinfunction "G_1") (pintype "input"))
      (node (ref "R1") (pin "2") (pinfunction "2_2") (pintype "passive"))
      (node (ref "R2") (pin "2") (pinfunction "2_2") (pintype "passive"))
    )
    (net (code "62") (name "Net-(U5A-~{RST})") (class "Default")
      (node (ref "R4") (pin "1") (pinfunction "1_1") (pintype "passive"))
      (node (ref "U5") (pin "9") (pinfunction "~{RST}_9") (pintype "bidirectional"))
    )
    (net (code "63") (name "Net-(U15-CSB)") (class "Default")
      (node (ref "R123") (pin "1") (pinfunction "1_1") (pintype "passive"))
      (node (ref "U15") (pin "2") (pinfunction "CSB_2") (pintype "input"))
      (node (ref "U15") (pin "5") (pinfunction "SDO_5") (pintype "bidirectional"))
    )
    (net (code "64") (name "Net-(VT1-B)") (class "Default")
      (node (ref "R28") (pin "2") (pinfunction "2_2") (pintype "passive"))
      (node (ref "VT1") (pin "1") (pinfunction "B_1") (pintype "passive"))
    )
    (net (code "65") (name "Net-(VT1-C)") (class "Default")
      (node (ref "LS1") (pin "2") (pinfunction "2_2") (pintype "passive"))
      (node (ref "VT1") (pin "3") (pinfunction "C_3") (pintype "passive"))
    )
    (net (code "66") (name "Net-(VT2-B)") (class "Default")
      (node (ref "R35") (pin "1") (pinfunction "1_1") (pintype "passive"))
      (node (ref "VT2") (pin "1") (pinfunction "B_1") (pintype "passive"))
    )
    (net (code "67") (name "Net-(VT3-B)") (class "Default")
      (node (ref "R34") (pin "2") (pinfunction "2_2") (pintype "passive"))
      (node (ref "VT3") (pin "1") (pinfunction "B_1") (pintype "passive"))
    )
    (net (code "68") (name "VBUS") (class "Default")
      (node (ref "C11") (pin "2") (pinfunction "2_2") (pintype "passive"))
      (node (ref "C7") (pin "2") (pinfunction "2_2") (pintype "passive"))
      (node (ref "U5") (pin "8") (pinfunction "VBUS_8") (pintype "input"))
    )
    (net (code "69") (name "unconnected-(J4-CD-Pad9)") (class "Default")
      (node (ref "J4") (pin "9") (pinfunction "CD_9") (pintype "output"))
    )
    (net (code "70") (name "unconnected-(J4-DATA1-Pad8)") (class "Default")
      (node (ref "J4") (pin "8") (pinfunction "DATA1_8") (pintype "passive"))
    )
    (net (code "71") (name "unconnected-(J4-DATA2-Pad1)") (class "Default")
      (node (ref "J4") (pin "1") (pinfunction "DATA2_1") (pintype "passive"))
    )
    (net (code "72") (name "unconnected-(OLED1-NC-Pad7)") (class "Default")
      (node (ref "OLED1") (pin "7") (pinfunction "NC_7") (pintype "passive"))
    )
    (net (code "73") (name "unconnected-(U2-VDD3V3-Pad22)") (class "Default")
      (node (ref "U2") (pin "22") (pinfunction "VDD3V3_22") (pintype "power_in"))
    )
    (net (code "74") (name "unconnected-(U2-VUSB-Pad6)") (class "Default")
      (node (ref "U2") (pin "6") (pinfunction "VUSB_6") (pintype "power_in"))
    )
    (net (code "75") (name "unconnected-(U5A-SUSPEND-Pad12)") (class "Default")
      (node (ref "U5") (pin "12") (pinfunction "SUSPEND_12") (pintype "output"))
    )
    (net (code "76") (name "unconnected-(U5A-~{CTS}-Pad23)") (class "Default")
      (node (ref "U5") (pin "23") (pinfunction "~{CTS}_23") (pintype "input"))
    )
    (net (code "77") (name "unconnected-(U5A-~{DCD}-Pad1)") (class "Default")
      (node (ref "U5") (pin "1") (pinfunction "~{DCD}_1") (pintype "input"))
    )
    (net (code "78") (name "unconnected-(U5A-~{DSR}-Pad27)") (class "Default")
      (node (ref "U5") (pin "27") (pinfunction "~{DSR}_27") (pintype "input"))
    )
    (net (code "79") (name "unconnected-(U5A-~{RI}-Pad2)") (class "Default")
      (node (ref "U5") (pin "2") (pinfunction "~{RI}_2") (pintype "input"))
    )
    (net (code "80") (name "unconnected-(U5A-~{SUSPEND}-Pad11)") (class "Default")
      (node (ref "U5") (pin "11") (pinfunction "~{SUSPEND}_11") (pintype "output"))
    )
  )
)
